# SAMD20_Xplained_Pro_EDBG.net
KiCad netlist of a schematic drawn in Altium Designer
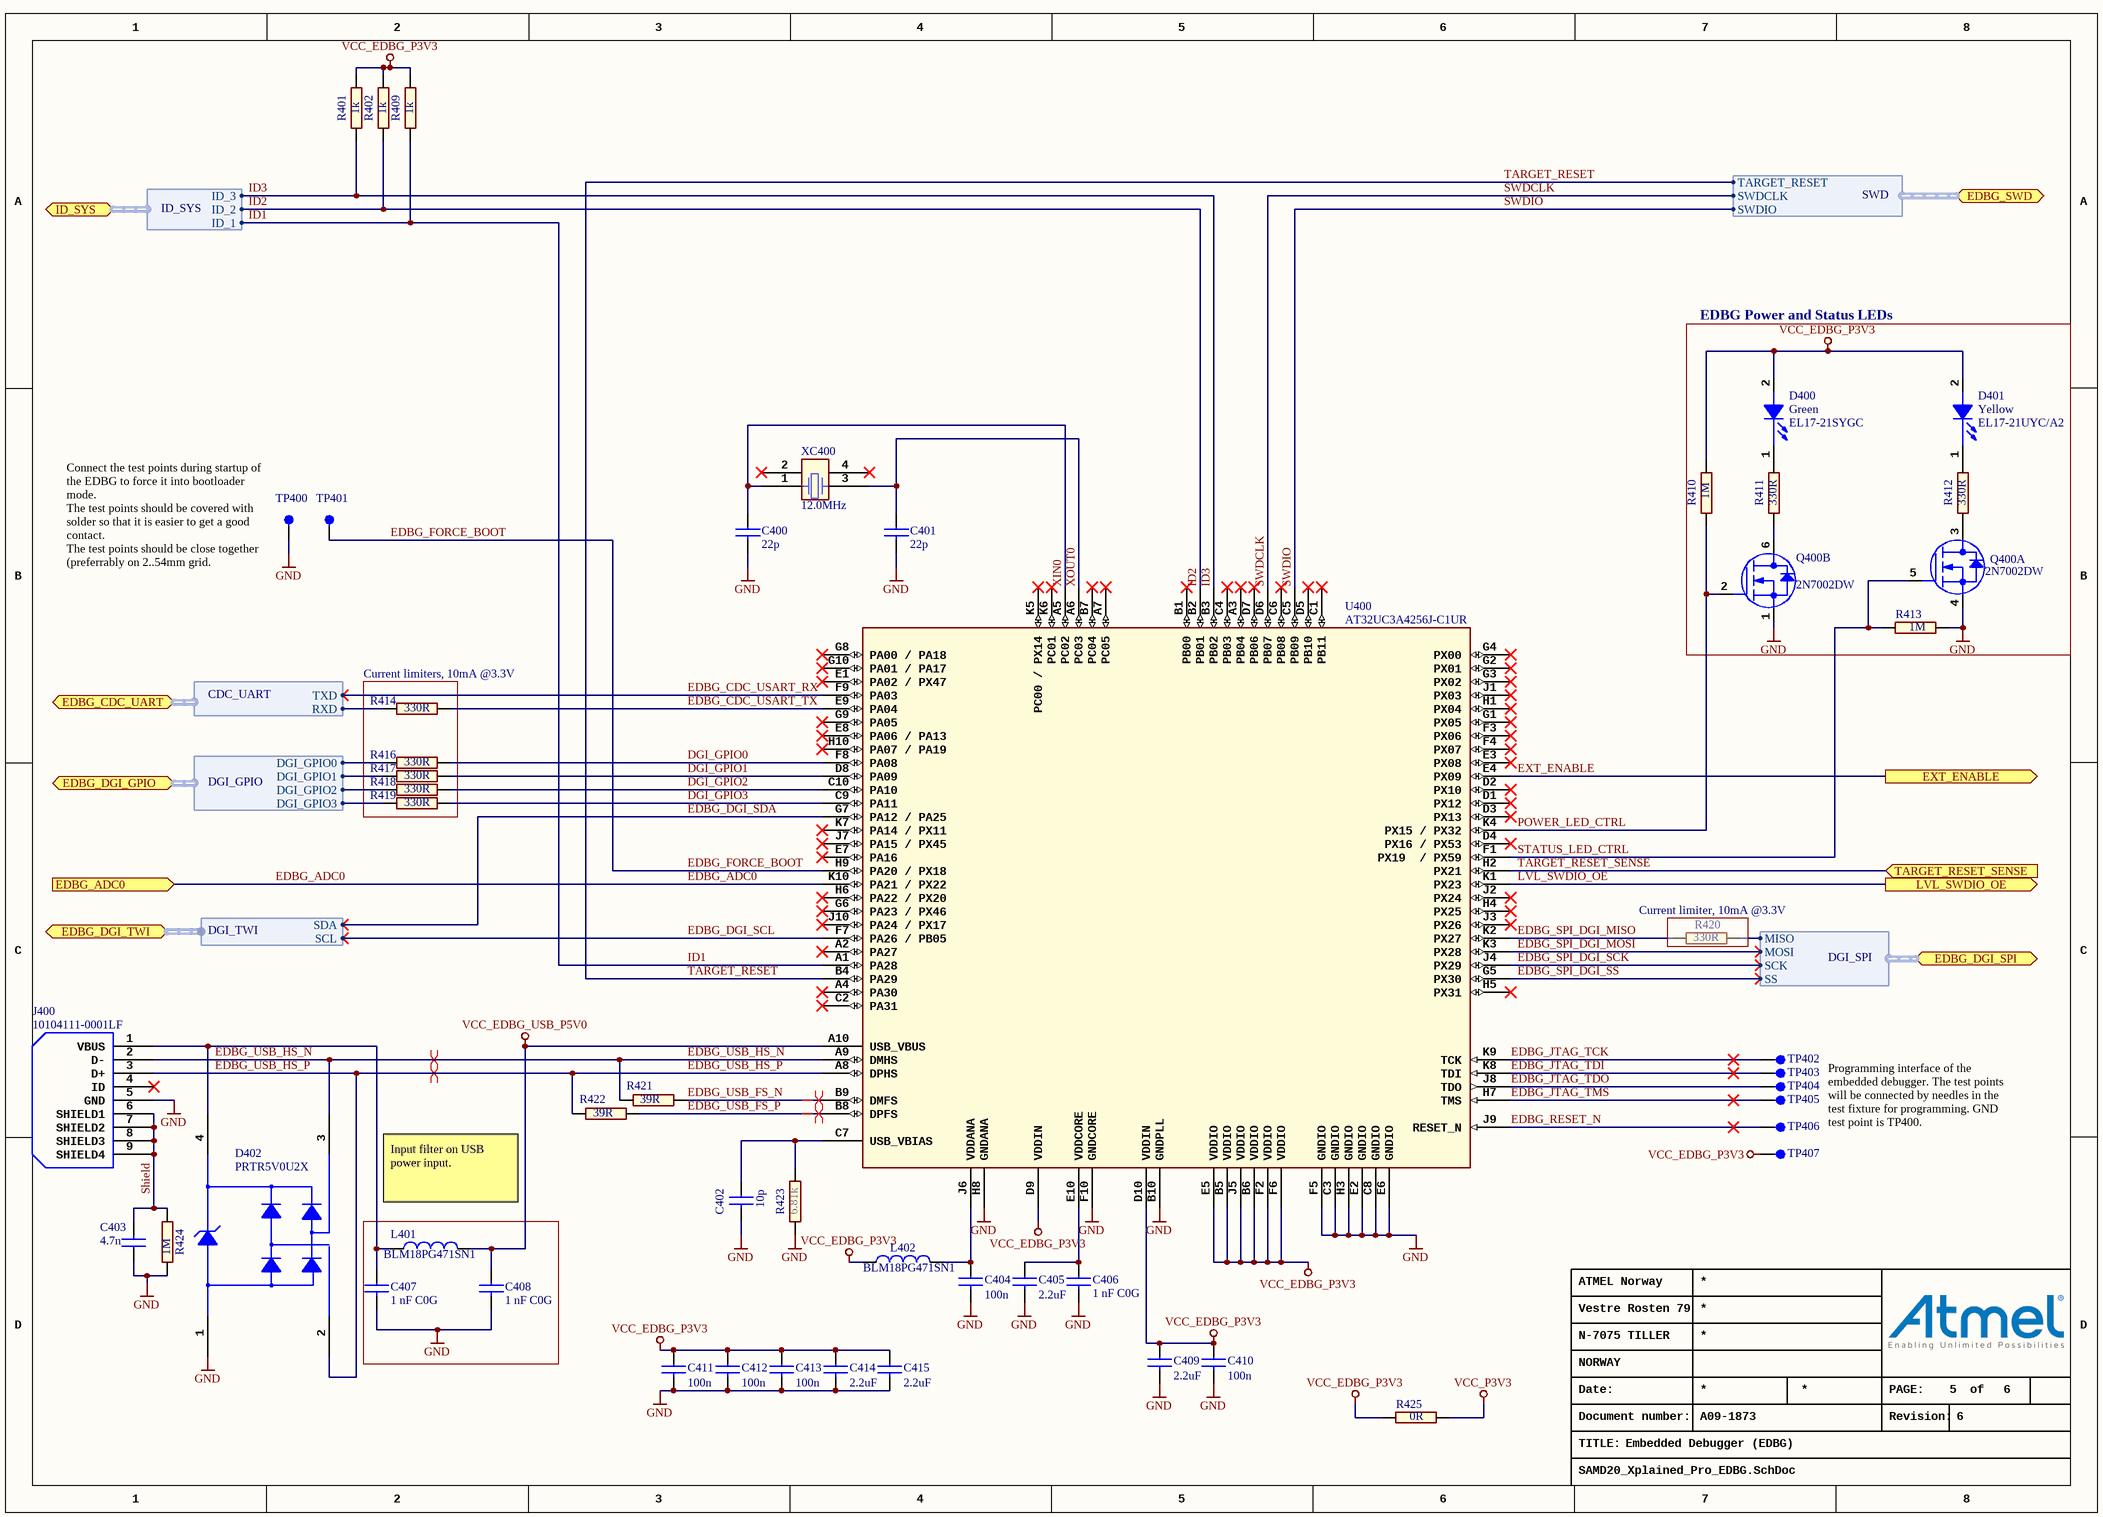
[diagram p0: SAMD20_Xplained_Pro_EDBG.SchDoc]

(export (version "E")
  (design (tool "Eeschema 10.0.6"))
  (components
    (comp (ref "C400")
      (value "22p")
      (footprint "AP1-00053")
      (description "Ceramic capacitor, SMD 0402, NP0, 50V, +/-5%")
      (fields (field (name "TOLERANCE") "50V, +/-5%"))
      (libsource (lib "AltiumDbLib") (part "CAP-NONPOL"))
    )
    (comp (ref "C401")
      (value "22p")
      (footprint "AP1-00053")
      (description "Ceramic capacitor, SMD 0402, NP0, 50V, +/-5%")
      (fields (field (name "TOLERANCE") "50V, +/-5%"))
      (libsource (lib "AltiumDbLib") (part "CAP-NONPOL"))
    )
    (comp (ref "C402")
      (value "10p")
      (footprint "AP1-00053")
      (description "Ceramic capacitor, SMD 0402, NP0, 50V, +/-5%")
      (fields (field (name "TOLERANCE") "50V, +/-5%"))
      (libsource (lib "AltiumDbLib") (part "CAP-NONPOL"))
    )
    (comp (ref "C403")
      (value "4.7n")
      (footprint "AP1-00053")
      (description "Ceramic capacitor, SMD 0402, X7R, 25V, +/-10%")
      (fields (field (name "TOLERANCE") "25V, +/-10%") (field (name "Comment") "CAP-NONPOL"))
      (libsource (lib "AltiumDbLib") (part "CAP-NONPOL"))
    )
    (comp (ref "C404")
      (value "100n")
      (footprint "AP1-00053")
      (description "Ceramic capacitor, SMD 0402, X7R, 16V, +/-10%")
      (fields (field (name "TOLERANCE") "16V, +/-10%") (field (name "MANUFACTURER") "Kemet"))
      (libsource (lib "AltiumDbLib") (part "CAP-NONPOL"))
    )
    (comp (ref "C405")
      (value "2.2uF")
      (footprint "AP1-00053")
      (description "Ceramic capacitor, SMD 0402, X5R, 6.3V, +/-20%")
      (fields (field (name "TOLERANCE") "±20%") (field (name "MANUFACTURER") "Kemet"))
      (libsource (lib "AltiumDbLib") (part "CAP-NONPOL"))
    )
    (comp (ref "C406")
      (value "1 nF C0G")
      (footprint "AP1-00053")
      (description "Ceramic capacitor, SMD 0402, C0G, 50V, +/-5%")
      (fields (field (name "TOLERANCE") "5%") (field (name "MANUFACTURER") "Murata"))
      (libsource (lib "AltiumDbLib") (part "CAP-NONPOL"))
    )
    (comp (ref "C407")
      (value "1 nF C0G")
      (footprint "AP1-00053")
      (description "Ceramic capacitor, SMD 0402, C0G, 50V, +/-5%")
      (fields (field (name "TOLERANCE") "5%") (field (name "MANUFACTURER") "Murata"))
      (libsource (lib "AltiumDbLib") (part "CAP-NONPOL"))
    )
    (comp (ref "C408")
      (value "1 nF C0G")
      (footprint "AP1-00053")
      (description "Ceramic capacitor, SMD 0402, C0G, 50V, +/-5%")
      (fields (field (name "TOLERANCE") "5%") (field (name "MANUFACTURER") "Murata"))
      (libsource (lib "AltiumDbLib") (part "CAP-NONPOL"))
    )
    (comp (ref "C409")
      (value "2.2uF")
      (footprint "AP1-00053")
      (description "Ceramic capacitor, SMD 0402, X5R, 6.3V, +/-20%")
      (fields (field (name "TOLERANCE") "±20%") (field (name "MANUFACTURER") "Kemet"))
      (libsource (lib "AltiumDbLib") (part "CAP-NONPOL"))
    )
    (comp (ref "C410")
      (value "100n")
      (footprint "AP1-00053")
      (description "Ceramic capacitor, SMD 0402, X7R, 16V, +/-10%")
      (fields (field (name "TOLERANCE") "16V, +/-10%") (field (name "MANUFACTURER") "Kemet"))
      (libsource (lib "AltiumDbLib") (part "CAP-NONPOL"))
    )
    (comp (ref "C411")
      (value "100n")
      (footprint "AP1-00053")
      (description "Ceramic capacitor, SMD 0402, X7R, 16V, +/-10%")
      (fields (field (name "TOLERANCE") "16V, +/-10%") (field (name "MANUFACTURER") "Kemet"))
      (libsource (lib "AltiumDbLib") (part "CAP-NONPOL"))
    )
    (comp (ref "C412")
      (value "100n")
      (footprint "AP1-00053")
      (description "Ceramic capacitor, SMD 0402, X7R, 16V, +/-10%")
      (fields (field (name "TOLERANCE") "16V, +/-10%") (field (name "MANUFACTURER") "Kemet"))
      (libsource (lib "AltiumDbLib") (part "CAP-NONPOL"))
    )
    (comp (ref "C413")
      (value "100n")
      (footprint "AP1-00053")
      (description "Ceramic capacitor, SMD 0402, X7R, 16V, +/-10%")
      (fields (field (name "TOLERANCE") "16V, +/-10%") (field (name "MANUFACTURER") "Kemet"))
      (libsource (lib "AltiumDbLib") (part "CAP-NONPOL"))
    )
    (comp (ref "C414")
      (value "2.2uF")
      (footprint "AP1-00053")
      (description "Ceramic capacitor, SMD 0402, X5R, 6.3V, +/-20%")
      (fields (field (name "TOLERANCE") "±20%") (field (name "MANUFACTURER") "Kemet"))
      (libsource (lib "AltiumDbLib") (part "CAP-NONPOL"))
    )
    (comp (ref "C415")
      (value "2.2uF")
      (footprint "AP1-00053")
      (description "Ceramic capacitor, SMD 0402, X5R, 6.3V, +/-20%")
      (fields (field (name "TOLERANCE") "±20%") (field (name "MANUFACTURER") "Kemet"))
      (libsource (lib "AltiumDbLib") (part "CAP-NONPOL"))
    )
    (comp (ref "D400")
      (value "Green")
      (footprint "AP4-00013")
      (description "LED, Green, Wave length=575nm, SMD 0805, ±70°")
      (fields
        (field (name "ALTIUM_VALUE") "EL17-21SYGC")
        (field (name "MANUFACTURER") "Everlight")
        (field (name "MPN") "EL17-21SYGC")
      )
      (libsource (lib "AltiumDbLib") (part "LED_12"))
    )
    (comp (ref "D401")
      (value "Yellow")
      (footprint "AP4-00013")
      (description "LED, Yellow, Wave length=591nm, SMD 0805, ±70°")
      (fields
        (field (name "ALTIUM_VALUE") "EL17-21UYC/A2")
        (field (name "MANUFACTURER") "Everlight")
        (field (name "MPN") "17-21UYC/S530-A3/TR8")
      )
      (libsource (lib "AltiumDbLib") (part "LED_12"))
    )
    (comp (ref "D402")
      (value "PRTR5V0U2X")
      (footprint "AP4-00001")
      (description "Double rail-to-rail USB ESD protection diode")
      (fields (field (name "MANUFACTURER") "Philips"))
      (libsource (lib "AltiumDbLib") (part "PRTR5V0U2X"))
    )
    (comp (ref "J400")
      (value "10104111-0001LF")
      (footprint "AP8-00604")
      (description "Micro USB AB Connector")
      (fields (field (name "MANUFACTURER") "FCI") (field (name "Comment") "USB_AB"))
      (libsource (lib "AltiumDbLib") (part "USB_AB"))
    )
    (comp (ref "L401")
      (value "BLM18PG471SN1")
      (footprint "AP3-00005")
      (description "SMD RF inductor 0603. Z=470Ohm (@100MHz), Max R(dc)=0.65Ohm, Max current=1A")
      (fields (field (name "TOLERANCE") "±25%") (field (name "MANUFACTURER") "Murata"))
      (libsource (lib "AltiumDbLib") (part "INDUCTOR"))
    )
    (comp (ref "L402")
      (value "BLM18PG471SN1")
      (footprint "AP3-00005")
      (description "SMD RF inductor 0603. Z=470Ohm (@100MHz), Max R(dc)=0.65Ohm, Max current=1A")
      (fields (field (name "TOLERANCE") "±25%") (field (name "MANUFACTURER") "Murata"))
      (libsource (lib "AltiumDbLib") (part "INDUCTOR"))
    )
    (comp (ref "Q400")
      (value "2N7002DW")
      (footprint "AP5-00001")
      (description "Dual N-Channel MOSFET, 60V, 115mA cont,RDS(ON) < 7.5 Ohm @50mA@5V, SOT-363")
      (fields
        (field (name "MANUFACTURER") "Fairchild")
        (field (name "Comment") "Same as 2N7002 but with two MOSFETs in one package")
      )
      (libsource (lib "AltiumDbLib") (part "MOSFET_DUAL_N_S2G2D1S1G1D2"))
    )
    (comp (ref "R401")
      (value "1k")
      (footprint "AP2-00000")
      (description "Thick film resistor, SMD 0402, 1/16W, 1%")
      (fields (field (name "TOLERANCE") "1 %") (field (name "Comment") "R2"))
      (libsource (lib "AltiumDbLib") (part "R2"))
    )
    (comp (ref "R402")
      (value "1k")
      (footprint "AP2-00000")
      (description "Thick film resistor, SMD 0402, 1/16W, 1%")
      (fields (field (name "TOLERANCE") "1 %") (field (name "Comment") "R2"))
      (libsource (lib "AltiumDbLib") (part "R2"))
    )
    (comp (ref "R409")
      (value "1k")
      (footprint "AP2-00000")
      (description "Thick film resistor, SMD 0402, 1/16W, 1%")
      (fields (field (name "TOLERANCE") "1 %") (field (name "Comment") "R2"))
      (libsource (lib "AltiumDbLib") (part "R2"))
    )
    (comp (ref "R410")
      (value "1M")
      (footprint "AP2-00000")
      (description "Thick film resistor, SMD 0402, 1/16W, 1%")
      (fields (field (name "TOLERANCE") "1 %") (field (name "MANUFACTURER") "KOA"))
      (libsource (lib "AltiumDbLib") (part "R2"))
    )
    (comp (ref "R411")
      (value "330R")
      (footprint "AP2-00000")
      (description "Thick film resistor, SMD 0402, 1/16W, 1%")
      (fields (field (name "TOLERANCE") "1 %") (field (name "Comment") "R2"))
      (libsource (lib "AltiumDbLib") (part "R2"))
    )
    (comp (ref "R412")
      (value "330R")
      (footprint "AP2-00000")
      (description "Thick film resistor, SMD 0402, 1/16W, 1%")
      (fields (field (name "TOLERANCE") "1 %") (field (name "Comment") "R2"))
      (libsource (lib "AltiumDbLib") (part "R2"))
    )
    (comp (ref "R413")
      (value "1M")
      (footprint "AP2-00000")
      (description "Thick film resistor, SMD 0402, 1/16W, 1%")
      (fields (field (name "TOLERANCE") "1 %") (field (name "MANUFACTURER") "KOA"))
      (libsource (lib "") (part "R2_3"))
    )
    (comp (ref "R414")
      (value "330R")
      (footprint "AP2-00000")
      (description "Thick film resistor, SMD 0402, 1/16W, 1%")
      (fields (field (name "TOLERANCE") "1 %") (field (name "Comment") "R2"))
      (libsource (lib "") (part "R2_2"))
    )
    (comp (ref "R416")
      (value "330R")
      (footprint "AP2-00000")
      (description "Thick film resistor, SMD 0402, 1/16W, 1%")
      (fields (field (name "TOLERANCE") "1 %") (field (name "Comment") "R2"))
      (libsource (lib "") (part "R2_2"))
    )
    (comp (ref "R417")
      (value "330R")
      (footprint "AP2-00000")
      (description "Thick film resistor, SMD 0402, 1/16W, 1%")
      (fields (field (name "TOLERANCE") "1 %") (field (name "Comment") "R2"))
      (libsource (lib "") (part "R2_2"))
    )
    (comp (ref "R418")
      (value "330R")
      (footprint "AP2-00000")
      (description "Thick film resistor, SMD 0402, 1/16W, 1%")
      (fields (field (name "TOLERANCE") "1 %") (field (name "Comment") "R2"))
      (libsource (lib "") (part "R2_2"))
    )
    (comp (ref "R419")
      (value "330R")
      (footprint "AP2-00000")
      (description "Thick film resistor, SMD 0402, 1/16W, 1%")
      (fields (field (name "TOLERANCE") "1 %") (field (name "Comment") "R2"))
      (libsource (lib "") (part "R2_2"))
    )
    (comp (ref "R420")
      (value "330R")
      (footprint "AP2-00000")
      (description "Thick film resistor, SMD 0402, 1/16W, 1%")
      (fields (field (name "TOLERANCE") "1 %") (field (name "Comment") "R2"))
      (libsource (lib "") (part "R2_2"))
    )
    (comp (ref "R421")
      (value "39R")
      (footprint "AP2-00011")
      (description "Thick film resistor, SMD 0402, 1/16W, 1%")
      (fields (field (name "TOLERANCE") "1 %") (field (name "Comment") "R2"))
      (libsource (lib "") (part "R2_1"))
    )
    (comp (ref "R422")
      (value "39R")
      (footprint "AP2-00011")
      (description "Thick film resistor, SMD 0402, 1/16W, 1%")
      (fields (field (name "TOLERANCE") "1 %") (field (name "Comment") "R2"))
      (libsource (lib "") (part "R2_1"))
    )
    (comp (ref "R423")
      (value "6.81k")
      (footprint "AP2-00011")
      (description "Thick film resistor, SMD 0402, 1/16W, 1%")
      (fields (field (name "TOLERANCE") "1%") (field (name "Comment") "R2"))
      (libsource (lib "AltiumDbLib") (part "R2"))
    )
    (comp (ref "R424")
      (value "1M")
      (footprint "AP2-00011")
      (description "Thick film resistor, SMD 0402, 1/16W, 1%")
      (fields (field (name "TOLERANCE") "1 %") (field (name "MANUFACTURER") "KOA"))
      (libsource (lib "") (part "R2_4"))
    )
    (comp (ref "R425")
      (value "0R")
      (footprint "AP2-00000")
      (description "Thick film resistor, SMD 0402, 1/16W, 1%")
      (fields (field (name "TOLERANCE") "1 %") (field (name "Comment") "R2"))
      (libsource (lib "") (part "R2_2"))
    )
    (comp (ref "TP400")
      (value "TESTPAD")
      (footprint "AP8-00010")
      (description "Single SMD testpad")
      (libsource (lib "AltiumDbLib") (part "TESTPOINT"))
    )
    (comp (ref "TP401")
      (value "TESTPAD")
      (footprint "AP8-00010")
      (description "Single SMD testpad")
      (libsource (lib "AltiumDbLib") (part "TESTPOINT"))
    )
    (comp (ref "TP402")
      (value "TESTPAD")
      (footprint "AP8-00010")
      (description "Single SMD testpad")
      (libsource (lib "AltiumDbLib") (part "TESTPOINT"))
    )
    (comp (ref "TP403")
      (value "TESTPAD")
      (footprint "AP8-00010")
      (description "Single SMD testpad")
      (libsource (lib "AltiumDbLib") (part "TESTPOINT"))
    )
    (comp (ref "TP404")
      (value "TESTPAD")
      (footprint "AP8-00010")
      (description "Single SMD testpad")
      (libsource (lib "AltiumDbLib") (part "TESTPOINT"))
    )
    (comp (ref "TP405")
      (value "TESTPAD")
      (footprint "AP8-00010")
      (description "Single SMD testpad")
      (libsource (lib "AltiumDbLib") (part "TESTPOINT"))
    )
    (comp (ref "TP406")
      (value "TESTPAD")
      (footprint "AP8-00010")
      (description "Single SMD testpad")
      (libsource (lib "AltiumDbLib") (part "TESTPOINT"))
    )
    (comp (ref "TP407")
      (value "TESTPAD")
      (footprint "AP8-00010")
      (description "Single SMD testpad")
      (libsource (lib "AltiumDbLib") (part "TESTPOINT"))
    )
    (comp (ref "U400")
      (value "AT32UC3A4256J-C1UR")
      (footprint "AP6-00206")
      (description "AVR 32-bit RISC MCU")
      (fields (field (name "MANUFACTURER") "ATMEL") (field (name "Comment") "100 ball VFBGA"))
      (libsource (lib "AltiumDbLib") (part "AT32UC3A4_VFBGA"))
    )
    (comp (ref "XC400")
      (value "12.0MHz")
      (footprint "AP7-00039")
      (description "Fox FQ5032B 12.0MHz SMD crystal 738B-12")
      (fields (field (name "TOLERANCE") "30PPM") (field (name "MANUFACTURER") "Fox  Electronics"))
      (libsource (lib "AltiumDbLib") (part "CRYSTAL1324"))
    )
  )
  (nets
    (net (code "7") (name "/DGI_GPIO0") (class "Default")
      (node (ref "R416") (pin "2") (pinfunction "2_2") (pintype "passive"))
      (node (ref "U400") (pin "F8") (pinfunction "PA08_F8") (pintype "bidirectional"))
    )
    (net (code "8") (name "/DGI_GPIO1") (class "Default")
      (node (ref "R417") (pin "2") (pinfunction "2_2") (pintype "passive"))
      (node (ref "U400") (pin "D8") (pinfunction "PA09_D8") (pintype "bidirectional"))
    )
    (net (code "9") (name "/DGI_GPIO2") (class "Default")
      (node (ref "R418") (pin "2") (pinfunction "2_2") (pintype "passive"))
      (node (ref "U400") (pin "C10") (pinfunction "PA10_C10") (pintype "bidirectional"))
    )
    (net (code "10") (name "/DGI_GPIO3") (class "Default")
      (node (ref "R419") (pin "2") (pinfunction "2_2") (pintype "passive"))
      (node (ref "U400") (pin "C9") (pinfunction "PA11_C9") (pintype "bidirectional"))
    )
    (net (code "11") (name "/EDBG_ADC0") (class "Default")
      (node (ref "U400") (pin "K10") (pinfunction "PA21_/_PX22_K10") (pintype "bidirectional"))
    )
    (net (code "12") (name "/EDBG_CDC_USART_RX") (class "Default")
      (node (ref "U400") (pin "F9") (pinfunction "PA03_F9") (pintype "bidirectional+no_connect"))
    )
    (net (code "13") (name "/EDBG_CDC_USART_TX") (class "Default")
      (node (ref "R414") (pin "2") (pinfunction "2_2") (pintype "passive"))
      (node (ref "U400") (pin "E9") (pinfunction "PA04_E9") (pintype "bidirectional"))
    )
    (net (code "14") (name "/EDBG_DGI_SCL") (class "Default")
      (node (ref "U400") (pin "F7") (pinfunction "PA26_/_PB05_F7") (pintype "bidirectional+no_connect"))
    )
    (net (code "15") (name "/EDBG_DGI_SDA") (class "Default")
      (node (ref "U400") (pin "G7") (pinfunction "PA12_/_PA25_G7") (pintype "bidirectional+no_connect"))
    )
    (net (code "16") (name "/EDBG_FORCE_BOOT") (class "Default")
      (node (ref "TP401") (pin "1") (pinfunction "1_1") (pintype "passive"))
      (node (ref "U400") (pin "H9") (pinfunction "PA20_/_PX18_H9") (pintype "bidirectional"))
    )
    (net (code "17") (name "/EDBG_JTAG_TCK") (class "Default")
      (node (ref "TP402") (pin "1") (pinfunction "1_1") (pintype "passive"))
      (node (ref "U400") (pin "K9") (pinfunction "TCK_K9") (pintype "input"))
    )
    (net (code "18") (name "/EDBG_JTAG_TDI") (class "Default")
      (node (ref "TP403") (pin "1") (pinfunction "1_1") (pintype "passive"))
      (node (ref "U400") (pin "K8") (pinfunction "TDI_K8") (pintype "input"))
    )
    (net (code "19") (name "/EDBG_JTAG_TDO") (class "Default")
      (node (ref "TP404") (pin "1") (pinfunction "1_1") (pintype "passive"))
      (node (ref "U400") (pin "J8") (pinfunction "TDO_J8") (pintype "output"))
    )
    (net (code "20") (name "/EDBG_JTAG_TMS") (class "Default")
      (node (ref "TP405") (pin "1") (pinfunction "1_1") (pintype "passive"))
      (node (ref "U400") (pin "H7") (pinfunction "TMS_H7") (pintype "input"))
    )
    (net (code "21") (name "/EDBG_RESET_N") (class "Default")
      (node (ref "TP406") (pin "1") (pinfunction "1_1") (pintype "passive"))
      (node (ref "U400") (pin "J9") (pinfunction "RESET_N_J9") (pintype "input"))
    )
    (net (code "22") (name "/EDBG_SPI_DGI_MISO") (class "Default")
      (node (ref "R420") (pin "1") (pinfunction "1_1") (pintype "passive"))
      (node (ref "U400") (pin "K2") (pinfunction "PX27_K2") (pintype "bidirectional"))
    )
    (net (code "23") (name "/EDBG_SPI_DGI_MOSI") (class "Default")
      (node (ref "U400") (pin "K3") (pinfunction "PX28_K3") (pintype "bidirectional+no_connect"))
    )
    (net (code "24") (name "/EDBG_SPI_DGI_SCK") (class "Default")
      (node (ref "U400") (pin "J4") (pinfunction "PX29_J4") (pintype "bidirectional+no_connect"))
    )
    (net (code "25") (name "/EDBG_SPI_DGI_SS") (class "Default")
      (node (ref "U400") (pin "G5") (pinfunction "PX30_G5") (pintype "bidirectional+no_connect"))
    )
    (net (code "26") (name "/EDBG_USB_FS_N") (class "Default")
      (node (ref "R421") (pin "2") (pinfunction "2_2") (pintype "passive"))
      (node (ref "U400") (pin "B9") (pinfunction "DMFS_B9") (pintype "bidirectional"))
    )
    (net (code "27") (name "/EDBG_USB_FS_P") (class "Default")
      (node (ref "R422") (pin "2") (pinfunction "2_2") (pintype "passive"))
      (node (ref "U400") (pin "B8") (pinfunction "DPFS_B8") (pintype "bidirectional"))
    )
    (net (code "28") (name "/EDBG_USB_HS_N") (class "Default")
      (node (ref "D402") (pin "3") (pinfunction "I/O_2_3") (pintype "passive"))
      (node (ref "J400") (pin "2") (pinfunction "D-_2") (pintype "passive"))
      (node (ref "R421") (pin "1") (pinfunction "1_1") (pintype "passive"))
      (node (ref "U400") (pin "A9") (pinfunction "DMHS_A9") (pintype "bidirectional"))
    )
    (net (code "29") (name "/EDBG_USB_HS_P") (class "Default")
      (node (ref "D402") (pin "2") (pinfunction "I/O_1_2") (pintype "passive"))
      (node (ref "J400") (pin "3") (pinfunction "D+_3") (pintype "passive"))
      (node (ref "R422") (pin "1") (pinfunction "1_1") (pintype "passive"))
      (node (ref "U400") (pin "A8") (pinfunction "DPHS_A8") (pintype "bidirectional"))
    )
    (net (code "30") (name "/EXT_ENABLE") (class "Default")
      (node (ref "U400") (pin "E4") (pinfunction "PX09_E4") (pintype "bidirectional"))
    )
    (net (code "31") (name "/ID1") (class "Default")
      (node (ref "R409") (pin "1") (pinfunction "1_1") (pintype "passive"))
      (node (ref "U400") (pin "A1") (pinfunction "PA28_A1") (pintype "bidirectional"))
    )
    (net (code "32") (name "/ID2") (class "Default")
      (node (ref "R402") (pin "1") (pinfunction "1_1") (pintype "passive"))
      (node (ref "U400") (pin "B2") (pinfunction "PB01_B2") (pintype "bidirectional"))
    )
    (net (code "33") (name "/ID3") (class "Default")
      (node (ref "R401") (pin "1") (pinfunction "1_1") (pintype "passive"))
      (node (ref "U400") (pin "B3") (pinfunction "PB02_B3") (pintype "bidirectional"))
    )
    (net (code "34") (name "/LVL_SWDIO_OE") (class "Default")
      (node (ref "U400") (pin "K1") (pinfunction "PX23_K1") (pintype "bidirectional"))
    )
    (net (code "35") (name "/MISO") (class "Default")
      (node (ref "R420") (pin "2") (pinfunction "2_2") (pintype "passive"))
    )
    (net (code "36") (name "/POWER_LED_CTRL") (class "Default")
      (node (ref "Q400") (pin "2") (pinfunction "G2_2") (pintype "passive"))
      (node (ref "R410") (pin "1") (pinfunction "1_1") (pintype "passive"))
      (node (ref "U400") (pin "K4") (pinfunction "PX15_/_PX32_K4") (pintype "bidirectional"))
    )
    (net (code "37") (name "/RXD") (class "Default")
      (node (ref "R414") (pin "1") (pinfunction "1_1") (pintype "passive"))
    )
    (net (code "38") (name "/STATUS_LED_CTRL") (class "Default")
      (node (ref "Q400") (pin "5") (pinfunction "G1_5") (pintype "passive"))
      (node (ref "R413") (pin "2") (pinfunction "2_2") (pintype "passive"))
      (node (ref "U400") (pin "F1") (pinfunction "PX19__/_PX59_F1") (pintype "bidirectional"))
    )
    (net (code "39") (name "/SWDCLK") (class "Default")
      (node (ref "U400") (pin "D6") (pinfunction "PB07_D6") (pintype "bidirectional"))
    )
    (net (code "40") (name "/SWDIO") (class "Default")
      (node (ref "U400") (pin "C5") (pinfunction "PB09_C5") (pintype "bidirectional"))
    )
    (net (code "41") (name "/Shield") (class "Default")
      (node (ref "C403") (pin "2") (pinfunction "2_2") (pintype "passive"))
      (node (ref "J400") (pin "6") (pinfunction "SHIELD1_6") (pintype "passive"))
      (node (ref "J400") (pin "7") (pinfunction "SHIELD2_7") (pintype "passive"))
      (node (ref "J400") (pin "8") (pinfunction "SHIELD3_8") (pintype "passive"))
      (node (ref "J400") (pin "9") (pinfunction "SHIELD4_9") (pintype "passive"))
      (node (ref "R424") (pin "2") (pinfunction "2_2") (pintype "passive"))
    )
    (net (code "42") (name "/TARGET_RESET") (class "Default")
      (node (ref "U400") (pin "B4") (pinfunction "PA29_B4") (pintype "bidirectional"))
    )
    (net (code "43") (name "/TARGET_RESET_SENSE") (class "Default")
      (node (ref "U400") (pin "H2") (pinfunction "PX21_H2") (pintype "bidirectional"))
    )
    (net (code "44") (name "/XIN0") (class "Default")
      (node (ref "C400") (pin "1") (pinfunction "1_1") (pintype "passive"))
      (node (ref "U400") (pin "A5") (pinfunction "PC02_A5") (pintype "bidirectional"))
      (node (ref "XC400") (pin "1") (pinfunction "1_1") (pintype "passive"))
    )
    (net (code "45") (name "/XOUT0") (class "Default")
      (node (ref "C401") (pin "1") (pinfunction "1_1") (pintype "passive"))
      (node (ref "U400") (pin "A6") (pinfunction "PC03_A6") (pintype "bidirectional"))
      (node (ref "XC400") (pin "3") (pinfunction "3_3") (pintype "passive"))
    )
    (net (code "52") (name "GND") (class "Default")
      (node (ref "C400") (pin "2") (pinfunction "2_2") (pintype "passive"))
      (node (ref "C401") (pin "2") (pinfunction "2_2") (pintype "passive"))
      (node (ref "C402") (pin "2") (pinfunction "2_2") (pintype "passive"))
      (node (ref "C403") (pin "1") (pinfunction "1_1") (pintype "passive"))
      (node (ref "C404") (pin "2") (pinfunction "2_2") (pintype "passive"))
      (node (ref "C405") (pin "2") (pinfunction "2_2") (pintype "passive"))
      (node (ref "C406") (pin "2") (pinfunction "2_2") (pintype "passive"))
      (node (ref "C407") (pin "2") (pinfunction "2_2") (pintype "passive"))
      (node (ref "C408") (pin "2") (pinfunction "2_2") (pintype "passive"))
      (node (ref "C409") (pin "2") (pinfunction "2_2") (pintype "passive"))
      (node (ref "C410") (pin "2") (pinfunction "2_2") (pintype "passive"))
      (node (ref "C411") (pin "2") (pinfunction "2_2") (pintype "passive"))
      (node (ref "C412") (pin "2") (pinfunction "2_2") (pintype "passive"))
      (node (ref "C413") (pin "2") (pinfunction "2_2") (pintype "passive"))
      (node (ref "C414") (pin "2") (pinfunction "2_2") (pintype "passive"))
      (node (ref "C415") (pin "2") (pinfunction "2_2") (pintype "passive"))
      (node (ref "D402") (pin "1") (pinfunction "GND_1") (pintype "passive"))
      (node (ref "J400") (pin "5") (pinfunction "GND_5") (pintype "passive"))
      (node (ref "Q400") (pin "1") (pinfunction "S2_1") (pintype "passive"))
      (node (ref "Q400") (pin "4") (pinfunction "S1_4") (pintype "passive"))
      (node (ref "R413") (pin "1") (pinfunction "1_1") (pintype "passive"))
      (node (ref "R423") (pin "1") (pinfunction "1_1") (pintype "passive"))
      (node (ref "R424") (pin "1") (pinfunction "1_1") (pintype "passive"))
      (node (ref "TP400") (pin "1") (pinfunction "1_1") (pintype "passive"))
      (node (ref "U400") (pin "B10") (pinfunction "GNDPLL_B10") (pintype "power_in"))
      (node (ref "U400") (pin "C3") (pinfunction "GNDIO_C3") (pintype "power_in"))
      (node (ref "U400") (pin "C8") (pinfunction "GNDIO_C8") (pintype "power_in"))
      (node (ref "U400") (pin "E2") (pinfunction "GNDIO_E2") (pintype "power_in"))
      (node (ref "U400") (pin "E6") (pinfunction "GNDIO_E6") (pintype "power_in"))
      (node (ref "U400") (pin "F10") (pinfunction "GNDCORE_F10") (pintype "power_in"))
      (node (ref "U400") (pin "F5") (pinfunction "GNDIO_F5") (pintype "power_in"))
      (node (ref "U400") (pin "H3") (pinfunction "GNDIO_H3") (pintype "power_in"))
      (node (ref "U400") (pin "H8") (pinfunction "GNDANA_H8") (pintype "power_in"))
    )
    (net (code "53") (name "Net-(D400-CATHODE)") (class "Default")
      (node (ref "D400") (pin "1") (pinfunction "CATHODE_1") (pintype "passive"))
      (node (ref "R411") (pin "2") (pinfunction "2_2") (pintype "passive"))
    )
    (net (code "54") (name "Net-(D401-CATHODE)") (class "Default")
      (node (ref "D401") (pin "1") (pinfunction "CATHODE_1") (pintype "passive"))
      (node (ref "R412") (pin "2") (pinfunction "2_2") (pintype "passive"))
    )
    (net (code "55") (name "Net-(D402-VCC)") (class "Default")
      (node (ref "C407") (pin "1") (pinfunction "1_1") (pintype "passive"))
      (node (ref "D402") (pin "4") (pinfunction "VCC_4") (pintype "passive"))
      (node (ref "J400") (pin "1") (pinfunction "VBUS_1") (pintype "passive"))
      (node (ref "L401") (pin "1") (pinfunction "1_1") (pintype "passive"))
    )
    (net (code "56") (name "Net-(Q400A-D1)") (class "Default")
      (node (ref "Q400") (pin "3") (pinfunction "D1_3") (pintype "passive"))
      (node (ref "R412") (pin "1") (pinfunction "1_1") (pintype "passive"))
    )
    (net (code "57") (name "Net-(Q400B-D2)") (class "Default")
      (node (ref "Q400") (pin "6") (pinfunction "D2_6") (pintype "passive"))
      (node (ref "R411") (pin "1") (pinfunction "1_1") (pintype "passive"))
    )
    (net (code "58") (name "Net-(U400-USB_VBIAS)") (class "Default")
      (node (ref "C402") (pin "1") (pinfunction "1_1") (pintype "passive"))
      (node (ref "R423") (pin "2") (pinfunction "2_2") (pintype "passive"))
      (node (ref "U400") (pin "C7") (pinfunction "USB_VBIAS_C7") (pintype "power_in"))
    )
    (net (code "59") (name "Net-(U400-VDDANA)") (class "Default")
      (node (ref "C404") (pin "1") (pinfunction "1_1") (pintype "passive"))
      (node (ref "L402") (pin "2") (pinfunction "2_2") (pintype "passive"))
      (node (ref "U400") (pin "J6") (pinfunction "VDDANA_J6") (pintype "power_in"))
    )
    (net (code "60") (name "Net-(U400-VDDCORE)") (class "Default")
      (node (ref "C405") (pin "1") (pinfunction "1_1") (pintype "passive"))
      (node (ref "C406") (pin "1") (pinfunction "1_1") (pintype "passive"))
      (node (ref "U400") (pin "E10") (pinfunction "VDDCORE_E10") (pintype "power_in"))
    )
    (net (code "61") (name "VCC_EDBG_P3V3") (class "Default")
      (node (ref "C409") (pin "1") (pinfunction "1_1") (pintype "passive"))
      (node (ref "C410") (pin "1") (pinfunction "1_1") (pintype "passive"))
      (node (ref "C411") (pin "1") (pinfunction "1_1") (pintype "passive"))
      (node (ref "C412") (pin "1") (pinfunction "1_1") (pintype "passive"))
      (node (ref "C413") (pin "1") (pinfunction "1_1") (pintype "passive"))
      (node (ref "C414") (pin "1") (pinfunction "1_1") (pintype "passive"))
      (node (ref "C415") (pin "1") (pinfunction "1_1") (pintype "passive"))
      (node (ref "D400") (pin "2") (pinfunction "ANODE_2") (pintype "passive"))
      (node (ref "D401") (pin "2") (pinfunction "ANODE_2") (pintype "passive"))
      (node (ref "L402") (pin "1") (pinfunction "1_1") (pintype "passive"))
      (node (ref "R401") (pin "2") (pinfunction "2_2") (pintype "passive"))
      (node (ref "R402") (pin "2") (pinfunction "2_2") (pintype "passive"))
      (node (ref "R409") (pin "2") (pinfunction "2_2") (pintype "passive"))
      (node (ref "R410") (pin "2") (pinfunction "2_2") (pintype "passive"))
      (node (ref "R425") (pin "1") (pinfunction "1_1") (pintype "passive"))
      (node (ref "TP407") (pin "1") (pinfunction "1_1") (pintype "passive"))
      (node (ref "U400") (pin "B5") (pinfunction "VDDIO_B5") (pintype "power_in"))
      (node (ref "U400") (pin "B6") (pinfunction "VDDIO_B6") (pintype "power_in"))
      (node (ref "U400") (pin "D10") (pinfunction "VDDIN_D10") (pintype "power_in"))
      (node (ref "U400") (pin "D9") (pinfunction "VDDIN_D9") (pintype "power_in"))
      (node (ref "U400") (pin "E5") (pinfunction "VDDIO_E5") (pintype "power_in"))
      (node (ref "U400") (pin "F2") (pinfunction "VDDIO_F2") (pintype "power_in"))
      (node (ref "U400") (pin "F6") (pinfunction "VDDIO_F6") (pintype "power_in"))
      (node (ref "U400") (pin "J5") (pinfunction "VDDIO_J5") (pintype "power_in"))
    )
    (net (code "62") (name "VCC_EDBG_USB_P5V0") (class "Default")
      (node (ref "C408") (pin "1") (pinfunction "1_1") (pintype "passive"))
      (node (ref "L401") (pin "2") (pinfunction "2_2") (pintype "passive"))
      (node (ref "U400") (pin "A10") (pinfunction "USB_VBUS_A10") (pintype "power_in"))
    )
    (net (code "63") (name "VCC_P3V3") (class "Default")
      (node (ref "R425") (pin "2") (pinfunction "2_2") (pintype "passive"))
    )
    (net (code "64") (name "unconnected-(J400-ID-Pad4)") (class "Default")
      (node (ref "J400") (pin "4") (pinfunction "ID_4") (pintype "passive+no_connect"))
    )
    (net (code "65") (name "unconnected-(R416-Pad1)") (class "Default")
      (node (ref "R416") (pin "1") (pinfunction "1_1") (pintype "passive"))
    )
    (net (code "66") (name "unconnected-(R417-Pad1)") (class "Default")
      (node (ref "R417") (pin "1") (pinfunction "1_1") (pintype "passive"))
    )
    (net (code "67") (name "unconnected-(R418-Pad1)") (class "Default")
      (node (ref "R418") (pin "1") (pinfunction "1_1") (pintype "passive"))
    )
    (net (code "68") (name "unconnected-(R419-Pad1)") (class "Default")
      (node (ref "R419") (pin "1") (pinfunction "1_1") (pintype "passive"))
    )
    (net (code "69") (name "unconnected-(U400-PA00_{slash}_PA18-PadG8)") (class "Default")
      (node (ref "U400") (pin "G8") (pinfunction "PA00_/_PA18_G8") (pintype "bidirectional+no_connect"))
    )
    (net (code "70") (name "unconnected-(U400-PA01_{slash}_PA17-PadG10)") (class "Default")
      (node (ref "U400") (pin "G10") (pinfunction "PA01_/_PA17_G10") (pintype "bidirectional+no_connect"))
    )
    (net (code "71") (name "unconnected-(U400-PA02_{slash}_PX47-PadE1)") (class "Default")
      (node (ref "U400") (pin "E1") (pinfunction "PA02_/_PX47_E1") (pintype "bidirectional+no_connect"))
    )
    (net (code "72") (name "unconnected-(U400-PA05-PadG9)") (class "Default")
      (node (ref "U400") (pin "G9") (pinfunction "PA05_G9") (pintype "bidirectional+no_connect"))
    )
    (net (code "73") (name "unconnected-(U400-PA06_{slash}_PA13-PadE8)") (class "Default")
      (node (ref "U400") (pin "E8") (pinfunction "PA06_/_PA13_E8") (pintype "bidirectional+no_connect"))
    )
    (net (code "74") (name "unconnected-(U400-PA07_{slash}_PA19-PadH10)") (class "Default")
      (node (ref "U400") (pin "H10") (pinfunction "PA07_/_PA19_H10") (pintype "bidirectional+no_connect"))
    )
    (net (code "75") (name "unconnected-(U400-PA14_{slash}_PX11-PadK7)") (class "Default")
      (node (ref "U400") (pin "K7") (pinfunction "PA14_/_PX11_K7") (pintype "bidirectional+no_connect"))
    )
    (net (code "76") (name "unconnected-(U400-PA15_{slash}_PX45-PadJ7)") (class "Default")
      (node (ref "U400") (pin "J7") (pinfunction "PA15_/_PX45_J7") (pintype "bidirectional+no_connect"))
    )
    (net (code "77") (name "unconnected-(U400-PA16-PadE7)") (class "Default")
      (node (ref "U400") (pin "E7") (pinfunction "PA16_E7") (pintype "bidirectional+no_connect"))
    )
    (net (code "78") (name "unconnected-(U400-PA22_{slash}_PX20-PadH6)") (class "Default")
      (node (ref "U400") (pin "H6") (pinfunction "PA22_/_PX20_H6") (pintype "bidirectional+no_connect"))
    )
    (net (code "79") (name "unconnected-(U400-PA23_{slash}_PX46-PadG6)") (class "Default")
      (node (ref "U400") (pin "G6") (pinfunction "PA23_/_PX46_G6") (pintype "bidirectional+no_connect"))
    )
    (net (code "80") (name "unconnected-(U400-PA24_{slash}_PX17-PadJ10)") (class "Default")
      (node (ref "U400") (pin "J10") (pinfunction "PA24_/_PX17_J10") (pintype "bidirectional+no_connect"))
    )
    (net (code "81") (name "unconnected-(U400-PA27-PadA2)") (class "Default")
      (node (ref "U400") (pin "A2") (pinfunction "PA27_A2") (pintype "bidirectional+no_connect"))
    )
    (net (code "82") (name "unconnected-(U400-PA30-PadA4)") (class "Default")
      (node (ref "U400") (pin "A4") (pinfunction "PA30_A4") (pintype "bidirectional+no_connect"))
    )
    (net (code "83") (name "unconnected-(U400-PA31-PadC2)") (class "Default")
      (node (ref "U400") (pin "C2") (pinfunction "PA31_C2") (pintype "bidirectional+no_connect"))
    )
    (net (code "84") (name "unconnected-(U400-PB00-PadB1)") (class "Default")
      (node (ref "U400") (pin "B1") (pinfunction "PB00_B1") (pintype "bidirectional+no_connect"))
    )
    (net (code "85") (name "unconnected-(U400-PB03-PadC4)") (class "Default")
      (node (ref "U400") (pin "C4") (pinfunction "PB03_C4") (pintype "bidirectional+no_connect"))
    )
    (net (code "86") (name "unconnected-(U400-PB04-PadA3)") (class "Default")
      (node (ref "U400") (pin "A3") (pinfunction "PB04_A3") (pintype "bidirectional+no_connect"))
    )
    (net (code "87") (name "unconnected-(U400-PB06-PadD7)") (class "Default")
      (node (ref "U400") (pin "D7") (pinfunction "PB06_D7") (pintype "bidirectional+no_connect"))
    )
    (net (code "88") (name "unconnected-(U400-PB08-PadC6)") (class "Default")
      (node (ref "U400") (pin "C6") (pinfunction "PB08_C6") (pintype "bidirectional+no_connect"))
    )
    (net (code "89") (name "unconnected-(U400-PB10-PadD5)") (class "Default")
      (node (ref "U400") (pin "D5") (pinfunction "PB10_D5") (pintype "bidirectional+no_connect"))
    )
    (net (code "90") (name "unconnected-(U400-PB11-PadC1)") (class "Default")
      (node (ref "U400") (pin "C1") (pinfunction "PB11_C1") (pintype "bidirectional+no_connect"))
    )
    (net (code "91") (name "unconnected-(U400-PC00_{slash}_PX14-PadK5)") (class "Default")
      (node (ref "U400") (pin "K5") (pinfunction "PC00_/_PX14_K5") (pintype "bidirectional+no_connect"))
    )
    (net (code "92") (name "unconnected-(U400-PC01-PadK6)") (class "Default")
      (node (ref "U400") (pin "K6") (pinfunction "PC01_K6") (pintype "bidirectional+no_connect"))
    )
    (net (code "93") (name "unconnected-(U400-PC04-PadB7)") (class "Default")
      (node (ref "U400") (pin "B7") (pinfunction "PC04_B7") (pintype "bidirectional+no_connect"))
    )
    (net (code "94") (name "unconnected-(U400-PC05-PadA7)") (class "Default")
      (node (ref "U400") (pin "A7") (pinfunction "PC05_A7") (pintype "bidirectional+no_connect"))
    )
    (net (code "95") (name "unconnected-(U400-PX00-PadG4)") (class "Default")
      (node (ref "U400") (pin "G4") (pinfunction "PX00_G4") (pintype "bidirectional+no_connect"))
    )
    (net (code "96") (name "unconnected-(U400-PX01-PadG2)") (class "Default")
      (node (ref "U400") (pin "G2") (pinfunction "PX01_G2") (pintype "bidirectional+no_connect"))
    )
    (net (code "97") (name "unconnected-(U400-PX02-PadG3)") (class "Default")
      (node (ref "U400") (pin "G3") (pinfunction "PX02_G3") (pintype "bidirectional+no_connect"))
    )
    (net (code "98") (name "unconnected-(U400-PX03-PadJ1)") (class "Default")
      (node (ref "U400") (pin "J1") (pinfunction "PX03_J1") (pintype "bidirectional+no_connect"))
    )
    (net (code "99") (name "unconnected-(U400-PX04-PadH1)") (class "Default")
      (node (ref "U400") (pin "H1") (pinfunction "PX04_H1") (pintype "bidirectional+no_connect"))
    )
    (net (code "100") (name "unconnected-(U400-PX05-PadG1)") (class "Default")
      (node (ref "U400") (pin "G1") (pinfunction "PX05_G1") (pintype "bidirectional+no_connect"))
    )
    (net (code "101") (name "unconnected-(U400-PX06-PadF3)") (class "Default")
      (node (ref "U400") (pin "F3") (pinfunction "PX06_F3") (pintype "bidirectional+no_connect"))
    )
    (net (code "102") (name "unconnected-(U400-PX07-PadF4)") (class "Default")
      (node (ref "U400") (pin "F4") (pinfunction "PX07_F4") (pintype "bidirectional+no_connect"))
    )
    (net (code "103") (name "unconnected-(U400-PX08-PadE3)") (class "Default")
      (node (ref "U400") (pin "E3") (pinfunction "PX08_E3") (pintype "bidirectional+no_connect"))
    )
    (net (code "104") (name "unconnected-(U400-PX10-PadD2)") (class "Default")
      (node (ref "U400") (pin "D2") (pinfunction "PX10_D2") (pintype "bidirectional+no_connect"))
    )
    (net (code "105") (name "unconnected-(U400-PX12-PadD1)") (class "Default")
      (node (ref "U400") (pin "D1") (pinfunction "PX12_D1") (pintype "bidirectional+no_connect"))
    )
    (net (code "106") (name "unconnected-(U400-PX13-PadD3)") (class "Default")
      (node (ref "U400") (pin "D3") (pinfunction "PX13_D3") (pintype "bidirectional+no_connect"))
    )
    (net (code "107") (name "unconnected-(U400-PX16_{slash}_PX53-PadD4)") (class "Default")
      (node (ref "U400") (pin "D4") (pinfunction "PX16_/_PX53_D4") (pintype "bidirectional+no_connect"))
    )
    (net (code "108") (name "unconnected-(U400-PX24-PadJ2)") (class "Default")
      (node (ref "U400") (pin "J2") (pinfunction "PX24_J2") (pintype "bidirectional+no_connect"))
    )
    (net (code "109") (name "unconnected-(U400-PX25-PadH4)") (class "Default")
      (node (ref "U400") (pin "H4") (pinfunction "PX25_H4") (pintype "bidirectional+no_connect"))
    )
    (net (code "110") (name "unconnected-(U400-PX26-PadJ3)") (class "Default")
      (node (ref "U400") (pin "J3") (pinfunction "PX26_J3") (pintype "bidirectional+no_connect"))
    )
    (net (code "111") (name "unconnected-(U400-PX31-PadH5)") (class "Default")
      (node (ref "U400") (pin "H5") (pinfunction "PX31_H5") (pintype "bidirectional+no_connect"))
    )
    (net (code "112") (name "unconnected-(XC400-Pad2)") (class "Default")
      (node (ref "XC400") (pin "2") (pinfunction "2_2") (pintype "passive+no_connect"))
    )
    (net (code "113") (name "unconnected-(XC400-Pad4)") (class "Default")
      (node (ref "XC400") (pin "4") (pinfunction "4_4") (pintype "passive+no_connect"))
    )
  )
)
